# M_E_ext_proto.net
KiCad netlist of a schematic drawn in EAGLE
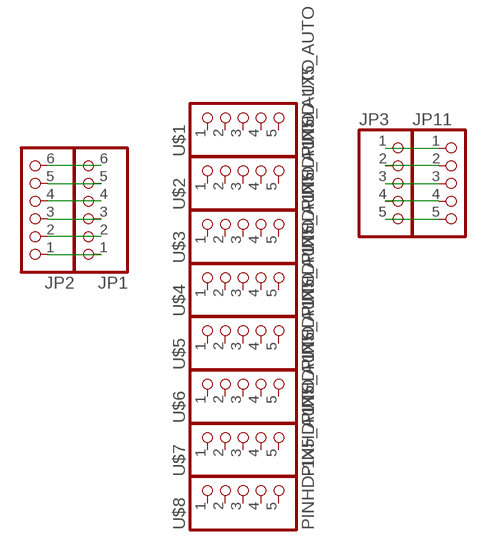
[diagram p0: schematic, sheet 1]

(export (version "E")
  (design (tool "Eeschema 10.0.6"))
  (components
    (comp (ref "JP1")
      (value "PINHD-1X6")
      (footprint "eagle-import:1X06")
      (libsource (lib "eagle-import") (part "PINHD-1X6"))
    )
    (comp (ref "JP2")
      (value "PINHD-1X6")
      (footprint "eagle-import:1X06")
      (libsource (lib "eagle-import") (part "PINHD-1X6"))
    )
    (comp (ref "JP3")
      (value "PINHD-1X5")
      (footprint "eagle-import:1X05")
      (libsource (lib "eagle-import") (part "PINHD-1X5"))
    )
    (comp (ref "JP11")
      (value "PINHD-1X5")
      (footprint "eagle-import:1X05")
      (libsource (lib "eagle-import") (part "PINHD-1X5"))
    )
    (comp (ref "U$1")
      (value "PINHD-1X5_AUTO")
      (footprint "eagle-import:1X5_AUTO")
      (libsource (lib "eagle-import") (part "PINHD-1X5_AUTO"))
    )
    (comp (ref "U$2")
      (value "PINHD-1X5_AUTO")
      (footprint "eagle-import:1X5_AUTO")
      (libsource (lib "eagle-import") (part "PINHD-1X5_AUTO"))
    )
    (comp (ref "U$3")
      (value "PINHD-1X5_AUTO")
      (footprint "eagle-import:1X5_AUTO")
      (libsource (lib "eagle-import") (part "PINHD-1X5_AUTO"))
    )
    (comp (ref "U$4")
      (value "PINHD-1X5_AUTO")
      (footprint "eagle-import:1X5_AUTO")
      (libsource (lib "eagle-import") (part "PINHD-1X5_AUTO"))
    )
    (comp (ref "U$5")
      (value "PINHD-1X5_AUTO")
      (footprint "eagle-import:1X5_AUTO")
      (libsource (lib "eagle-import") (part "PINHD-1X5_AUTO"))
    )
    (comp (ref "U$6")
      (value "PINHD-1X5_AUTO")
      (footprint "eagle-import:1X5_AUTO")
      (libsource (lib "eagle-import") (part "PINHD-1X5_AUTO"))
    )
    (comp (ref "U$7")
      (value "PINHD-1X5_AUTO")
      (footprint "eagle-import:1X5_AUTO")
      (libsource (lib "eagle-import") (part "PINHD-1X5_AUTO"))
    )
    (comp (ref "U$8")
      (value "PINHD-1X5_AUTO")
      (footprint "eagle-import:1X5_AUTO")
      (libsource (lib "eagle-import") (part "PINHD-1X5_AUTO"))
    )
  )
  (nets
    (net (code "1") (name "Net-(JP1-Pad1)") (class "Default")
      (node (ref "JP1") (pin "1") (pinfunction "1_1") (pintype "passive"))
      (node (ref "JP2") (pin "1") (pinfunction "1_1") (pintype "passive"))
    )
    (net (code "2") (name "Net-(JP1-Pad2)") (class "Default")
      (node (ref "JP1") (pin "2") (pinfunction "2_2") (pintype "passive"))
      (node (ref "JP2") (pin "2") (pinfunction "2_2") (pintype "passive"))
    )
    (net (code "3") (name "Net-(JP1-Pad3)") (class "Default")
      (node (ref "JP1") (pin "3") (pinfunction "3_3") (pintype "passive"))
      (node (ref "JP2") (pin "3") (pinfunction "3_3") (pintype "passive"))
    )
    (net (code "4") (name "Net-(JP1-Pad4)") (class "Default")
      (node (ref "JP1") (pin "4") (pinfunction "4_4") (pintype "passive"))
      (node (ref "JP2") (pin "4") (pinfunction "4_4") (pintype "passive"))
    )
    (net (code "5") (name "Net-(JP1-Pad5)") (class "Default")
      (node (ref "JP1") (pin "5") (pinfunction "5_5") (pintype "passive"))
      (node (ref "JP2") (pin "5") (pinfunction "5_5") (pintype "passive"))
    )
    (net (code "6") (name "Net-(JP1-Pad6)") (class "Default")
      (node (ref "JP1") (pin "6") (pinfunction "6_6") (pintype "passive"))
      (node (ref "JP2") (pin "6") (pinfunction "6_6") (pintype "passive"))
    )
    (net (code "7") (name "Net-(JP11-Pad1)") (class "Default")
      (node (ref "JP11") (pin "1") (pinfunction "1_1") (pintype "passive"))
      (node (ref "JP3") (pin "1") (pinfunction "1_1") (pintype "passive"))
    )
    (net (code "8") (name "Net-(JP11-Pad2)") (class "Default")
      (node (ref "JP11") (pin "2") (pinfunction "2_2") (pintype "passive"))
      (node (ref "JP3") (pin "2") (pinfunction "2_2") (pintype "passive"))
    )
    (net (code "9") (name "Net-(JP11-Pad3)") (class "Default")
      (node (ref "JP11") (pin "3") (pinfunction "3_3") (pintype "passive"))
      (node (ref "JP3") (pin "3") (pinfunction "3_3") (pintype "passive"))
    )
    (net (code "10") (name "Net-(JP11-Pad4)") (class "Default")
      (node (ref "JP11") (pin "4") (pinfunction "4_4") (pintype "passive"))
      (node (ref "JP3") (pin "4") (pinfunction "4_4") (pintype "passive"))
    )
    (net (code "11") (name "Net-(JP11-Pad5)") (class "Default")
      (node (ref "JP11") (pin "5") (pinfunction "5_5") (pintype "passive"))
      (node (ref "JP3") (pin "5") (pinfunction "5_5") (pintype "passive"))
    )
    (net (code "12") (name "unconnected-(U$1-Pad1)") (class "Default")
      (node (ref "U$1") (pin "1") (pinfunction "1_1") (pintype "passive"))
    )
    (net (code "13") (name "unconnected-(U$1-Pad2)") (class "Default")
      (node (ref "U$1") (pin "2") (pinfunction "2_2") (pintype "passive"))
    )
    (net (code "14") (name "unconnected-(U$1-Pad3)") (class "Default")
      (node (ref "U$1") (pin "3") (pinfunction "3_3") (pintype "passive"))
    )
    (net (code "15") (name "unconnected-(U$1-Pad4)") (class "Default")
      (node (ref "U$1") (pin "4") (pinfunction "4_4") (pintype "passive"))
    )
    (net (code "16") (name "unconnected-(U$1-Pad5)") (class "Default")
      (node (ref "U$1") (pin "5") (pinfunction "5_5") (pintype "passive"))
    )
    (net (code "17") (name "unconnected-(U$2-Pad1)") (class "Default")
      (node (ref "U$2") (pin "1") (pinfunction "1_1") (pintype "passive"))
    )
    (net (code "18") (name "unconnected-(U$2-Pad2)") (class "Default")
      (node (ref "U$2") (pin "2") (pinfunction "2_2") (pintype "passive"))
    )
    (net (code "19") (name "unconnected-(U$2-Pad3)") (class "Default")
      (node (ref "U$2") (pin "3") (pinfunction "3_3") (pintype "passive"))
    )
    (net (code "20") (name "unconnected-(U$2-Pad4)") (class "Default")
      (node (ref "U$2") (pin "4") (pinfunction "4_4") (pintype "passive"))
    )
    (net (code "21") (name "unconnected-(U$2-Pad5)") (class "Default")
      (node (ref "U$2") (pin "5") (pinfunction "5_5") (pintype "passive"))
    )
    (net (code "22") (name "unconnected-(U$3-Pad1)") (class "Default")
      (node (ref "U$3") (pin "1") (pinfunction "1_1") (pintype "passive"))
    )
    (net (code "23") (name "unconnected-(U$3-Pad2)") (class "Default")
      (node (ref "U$3") (pin "2") (pinfunction "2_2") (pintype "passive"))
    )
    (net (code "24") (name "unconnected-(U$3-Pad3)") (class "Default")
      (node (ref "U$3") (pin "3") (pinfunction "3_3") (pintype "passive"))
    )
    (net (code "25") (name "unconnected-(U$3-Pad4)") (class "Default")
      (node (ref "U$3") (pin "4") (pinfunction "4_4") (pintype "passive"))
    )
    (net (code "26") (name "unconnected-(U$3-Pad5)") (class "Default")
      (node (ref "U$3") (pin "5") (pinfunction "5_5") (pintype "passive"))
    )
    (net (code "27") (name "unconnected-(U$4-Pad1)") (class "Default")
      (node (ref "U$4") (pin "1") (pinfunction "1_1") (pintype "passive"))
    )
    (net (code "28") (name "unconnected-(U$4-Pad2)") (class "Default")
      (node (ref "U$4") (pin "2") (pinfunction "2_2") (pintype "passive"))
    )
    (net (code "29") (name "unconnected-(U$4-Pad3)") (class "Default")
      (node (ref "U$4") (pin "3") (pinfunction "3_3") (pintype "passive"))
    )
    (net (code "30") (name "unconnected-(U$4-Pad4)") (class "Default")
      (node (ref "U$4") (pin "4") (pinfunction "4_4") (pintype "passive"))
    )
    (net (code "31") (name "unconnected-(U$4-Pad5)") (class "Default")
      (node (ref "U$4") (pin "5") (pinfunction "5_5") (pintype "passive"))
    )
    (net (code "32") (name "unconnected-(U$5-Pad1)") (class "Default")
      (node (ref "U$5") (pin "1") (pinfunction "1_1") (pintype "passive"))
    )
    (net (code "33") (name "unconnected-(U$5-Pad2)") (class "Default")
      (node (ref "U$5") (pin "2") (pinfunction "2_2") (pintype "passive"))
    )
    (net (code "34") (name "unconnected-(U$5-Pad3)") (class "Default")
      (node (ref "U$5") (pin "3") (pinfunction "3_3") (pintype "passive"))
    )
    (net (code "35") (name "unconnected-(U$5-Pad4)") (class "Default")
      (node (ref "U$5") (pin "4") (pinfunction "4_4") (pintype "passive"))
    )
    (net (code "36") (name "unconnected-(U$5-Pad5)") (class "Default")
      (node (ref "U$5") (pin "5") (pinfunction "5_5") (pintype "passive"))
    )
    (net (code "37") (name "unconnected-(U$6-Pad1)") (class "Default")
      (node (ref "U$6") (pin "1") (pinfunction "1_1") (pintype "passive"))
    )
    (net (code "38") (name "unconnected-(U$6-Pad2)") (class "Default")
      (node (ref "U$6") (pin "2") (pinfunction "2_2") (pintype "passive"))
    )
    (net (code "39") (name "unconnected-(U$6-Pad3)") (class "Default")
      (node (ref "U$6") (pin "3") (pinfunction "3_3") (pintype "passive"))
    )
    (net (code "40") (name "unconnected-(U$6-Pad4)") (class "Default")
      (node (ref "U$6") (pin "4") (pinfunction "4_4") (pintype "passive"))
    )
    (net (code "41") (name "unconnected-(U$6-Pad5)") (class "Default")
      (node (ref "U$6") (pin "5") (pinfunction "5_5") (pintype "passive"))
    )
    (net (code "42") (name "unconnected-(U$7-Pad1)") (class "Default")
      (node (ref "U$7") (pin "1") (pinfunction "1_1") (pintype "passive"))
    )
    (net (code "43") (name "unconnected-(U$7-Pad2)") (class "Default")
      (node (ref "U$7") (pin "2") (pinfunction "2_2") (pintype "passive"))
    )
    (net (code "44") (name "unconnected-(U$7-Pad3)") (class "Default")
      (node (ref "U$7") (pin "3") (pinfunction "3_3") (pintype "passive"))
    )
    (net (code "45") (name "unconnected-(U$7-Pad4)") (class "Default")
      (node (ref "U$7") (pin "4") (pinfunction "4_4") (pintype "passive"))
    )
    (net (code "46") (name "unconnected-(U$7-Pad5)") (class "Default")
      (node (ref "U$7") (pin "5") (pinfunction "5_5") (pintype "passive"))
    )
    (net (code "47") (name "unconnected-(U$8-Pad1)") (class "Default")
      (node (ref "U$8") (pin "1") (pinfunction "1_1") (pintype "passive"))
    )
    (net (code "48") (name "unconnected-(U$8-Pad2)") (class "Default")
      (node (ref "U$8") (pin "2") (pinfunction "2_2") (pintype "passive"))
    )
    (net (code "49") (name "unconnected-(U$8-Pad3)") (class "Default")
      (node (ref "U$8") (pin "3") (pinfunction "3_3") (pintype "passive"))
    )
    (net (code "50") (name "unconnected-(U$8-Pad4)") (class "Default")
      (node (ref "U$8") (pin "4") (pinfunction "4_4") (pintype "passive"))
    )
    (net (code "51") (name "unconnected-(U$8-Pad5)") (class "Default")
      (node (ref "U$8") (pin "5") (pinfunction "5_5") (pintype "passive"))
    )
  )
)
